# Adafruit_MagTag_2_9in_Rev_D.net
KiCad netlist of a schematic drawn in EAGLE
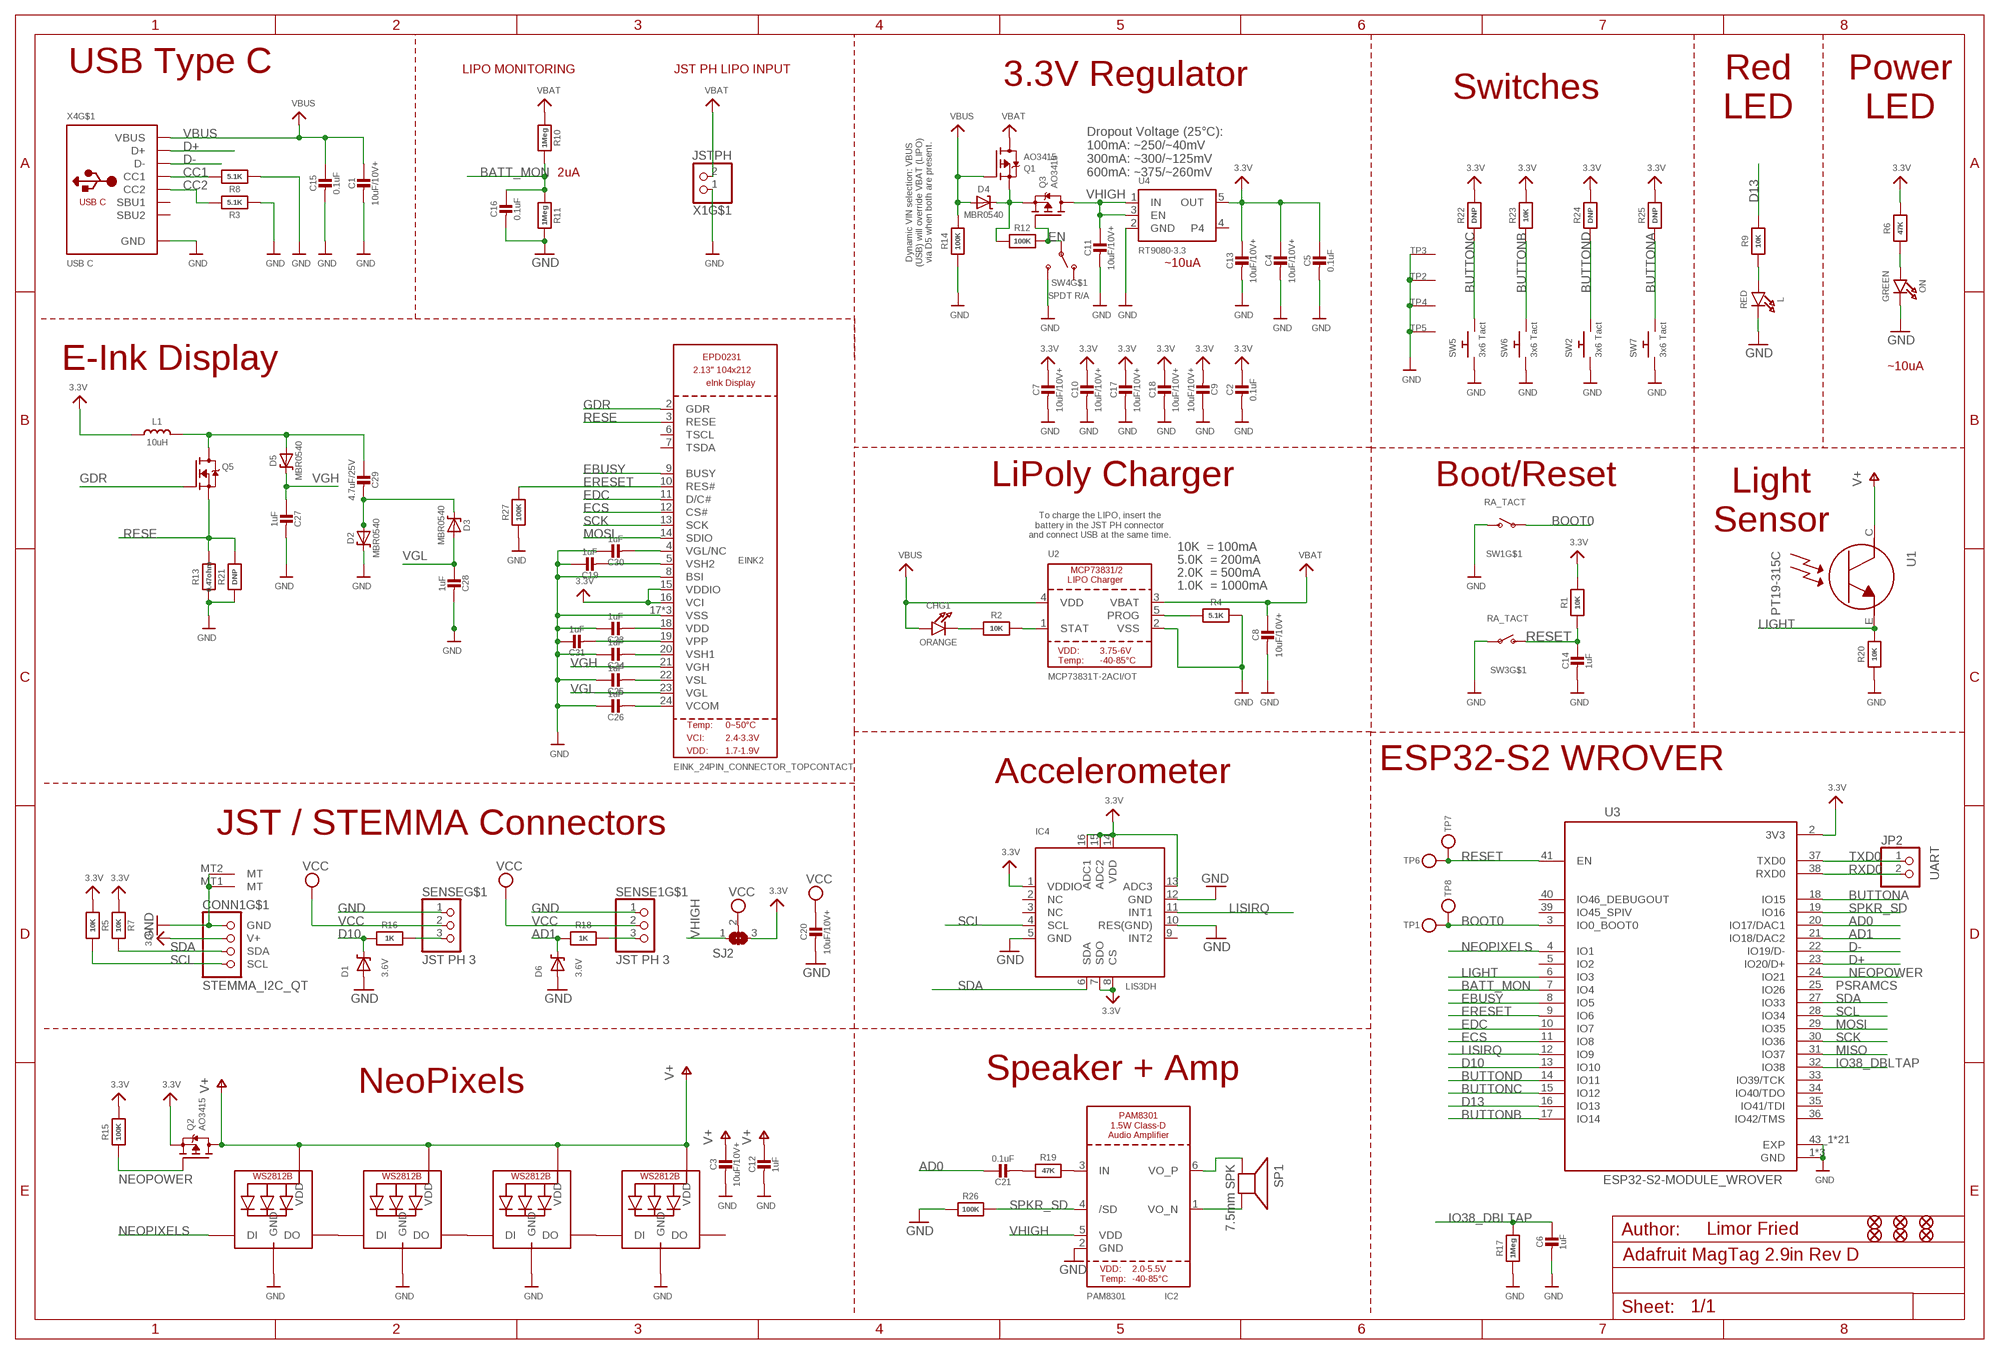
[diagram p0: schematic, sheet 1]

(export (version "E")
  (design (tool "Eeschema 10.0.6"))
  (components
    (comp (ref "C1")
      (value "10uF/10V+")
      (footprint "eagle-import:0805-NO")
      (libsource (lib "eagle-import") (part "CAP_CERAMIC0805-NOOUTLINE"))
    )
    (comp (ref "C2")
      (value "0.1uF")
      (footprint "eagle-import:0603-NO")
      (libsource (lib "eagle-import") (part "CAP_CERAMIC0603_NO"))
    )
    (comp (ref "C3")
      (value "10uF/10V+")
      (footprint "eagle-import:0805-NO")
      (libsource (lib "eagle-import") (part "CAP_CERAMIC0805-NOOUTLINE"))
    )
    (comp (ref "C4")
      (value "10uF/10V+")
      (footprint "eagle-import:0805-NO")
      (libsource (lib "eagle-import") (part "CAP_CERAMIC0805-NOOUTLINE"))
    )
    (comp (ref "C5")
      (value "0.1uF")
      (footprint "eagle-import:0603-NO")
      (libsource (lib "eagle-import") (part "CAP_CERAMIC0603_NO"))
    )
    (comp (ref "C6")
      (value "1uF")
      (footprint "eagle-import:0603-NO")
      (libsource (lib "eagle-import") (part "CAP_CERAMIC0603_NO"))
    )
    (comp (ref "C7")
      (value "10uF/10V+")
      (footprint "eagle-import:0805-NO")
      (libsource (lib "eagle-import") (part "CAP_CERAMIC0805-NOOUTLINE"))
    )
    (comp (ref "C8")
      (value "10uF/10V+")
      (footprint "eagle-import:0805-NO")
      (libsource (lib "eagle-import") (part "CAP_CERAMIC0805-NOOUTLINE"))
    )
    (comp (ref "C9")
      (value "10uF/10V+")
      (footprint "eagle-import:0805-NO")
      (libsource (lib "eagle-import") (part "CAP_CERAMIC0805-NOOUTLINE"))
    )
    (comp (ref "C10")
      (value "10uF/10V+")
      (footprint "eagle-import:0805-NO")
      (libsource (lib "eagle-import") (part "CAP_CERAMIC0805-NOOUTLINE"))
    )
    (comp (ref "C11")
      (value "10uF/10V+")
      (footprint "eagle-import:0805-NO")
      (libsource (lib "eagle-import") (part "CAP_CERAMIC0805-NOOUTLINE"))
    )
    (comp (ref "C12")
      (value "1uF")
      (footprint "eagle-import:0603-NO")
      (libsource (lib "eagle-import") (part "CAP_CERAMIC0603_NO"))
    )
    (comp (ref "C13")
      (value "10uF/10V+")
      (footprint "eagle-import:0805-NO")
      (libsource (lib "eagle-import") (part "CAP_CERAMIC0805-NOOUTLINE"))
    )
    (comp (ref "C14")
      (value "1uF")
      (footprint "eagle-import:0603-NO")
      (libsource (lib "eagle-import") (part "CAP_CERAMIC0603_NO"))
    )
    (comp (ref "C15")
      (value "0.1uF")
      (footprint "eagle-import:0603-NO")
      (libsource (lib "eagle-import") (part "CAP_CERAMIC0603_NO"))
    )
    (comp (ref "C16")
      (value "0.1uF")
      (footprint "eagle-import:0603-NO")
      (libsource (lib "eagle-import") (part "CAP_CERAMIC0603_NO"))
    )
    (comp (ref "C17")
      (value "10uF/10V+")
      (footprint "eagle-import:0805-NO")
      (libsource (lib "eagle-import") (part "CAP_CERAMIC0805-NOOUTLINE"))
    )
    (comp (ref "C18")
      (value "10uF/10V+")
      (footprint "eagle-import:0805-NO")
      (libsource (lib "eagle-import") (part "CAP_CERAMIC0805-NOOUTLINE"))
    )
    (comp (ref "C19")
      (value "1uF")
      (footprint "eagle-import:0805-NO")
      (libsource (lib "eagle-import") (part "CAP_CERAMIC0805-NOOUTLINE"))
    )
    (comp (ref "C20")
      (value "10uF/10V+")
      (footprint "eagle-import:0805-NO")
      (libsource (lib "eagle-import") (part "CAP_CERAMIC0805-NOOUTLINE"))
    )
    (comp (ref "C21")
      (value "0.1uF")
      (footprint "eagle-import:0603-NO")
      (libsource (lib "eagle-import") (part "CAP_CERAMIC0603_NO"))
    )
    (comp (ref "C23")
      (value "1uF")
      (footprint "eagle-import:0805-NO")
      (libsource (lib "eagle-import") (part "CAP_CERAMIC0805-NOOUTLINE"))
    )
    (comp (ref "C24")
      (value "1uF")
      (footprint "eagle-import:0805-NO")
      (libsource (lib "eagle-import") (part "CAP_CERAMIC0805-NOOUTLINE"))
    )
    (comp (ref "C25")
      (value "1uF")
      (footprint "eagle-import:0805-NO")
      (libsource (lib "eagle-import") (part "CAP_CERAMIC0805-NOOUTLINE"))
    )
    (comp (ref "C26")
      (value "1uF")
      (footprint "eagle-import:0805-NO")
      (libsource (lib "eagle-import") (part "CAP_CERAMIC0805-NOOUTLINE"))
    )
    (comp (ref "C27")
      (value "1uF")
      (footprint "eagle-import:0805-NO")
      (libsource (lib "eagle-import") (part "CAP_CERAMIC0805-NOOUTLINE"))
    )
    (comp (ref "C28")
      (value "1uF")
      (footprint "eagle-import:0805-NO")
      (libsource (lib "eagle-import") (part "CAP_CERAMIC0805-NOOUTLINE"))
    )
    (comp (ref "C29")
      (value "4.7uF/25V")
      (footprint "eagle-import:0805-NO")
      (libsource (lib "eagle-import") (part "CAP_CERAMIC0805-NOOUTLINE"))
    )
    (comp (ref "C30")
      (value "1uF")
      (footprint "eagle-import:0805-NO")
      (libsource (lib "eagle-import") (part "CAP_CERAMIC0805-NOOUTLINE"))
    )
    (comp (ref "C31")
      (value "1uF")
      (footprint "eagle-import:0805-NO")
      (libsource (lib "eagle-import") (part "CAP_CERAMIC0805-NOOUTLINE"))
    )
    (comp (ref "CHG1")
      (value "ORANGE")
      (footprint "eagle-import:CHIPLED_0603_NOOUTLINE")
      (libsource (lib "eagle-import") (part "LED0603_NOOUTLINE"))
    )
    (comp (ref "CONN1")
      (value "STEMMA_I2C_QT")
      (footprint "eagle-import:JST_SH4")
      (libsource (lib "eagle-import") (part "STEMMA_I2C_QT"))
    )
    (comp (ref "D1")
      (value "3.6V")
      (footprint "eagle-import:SOD-323")
      (libsource (lib "eagle-import") (part "DIODE-ZENERSOD323"))
    )
    (comp (ref "D2")
      (value "MBR0540")
      (footprint "eagle-import:SOD-123")
      (libsource (lib "eagle-import") (part "DIODE-SCHOTTKYSOD-123"))
    )
    (comp (ref "D3")
      (value "MBR0540")
      (footprint "eagle-import:SOD-123")
      (libsource (lib "eagle-import") (part "DIODE-SCHOTTKYSOD-123"))
    )
    (comp (ref "D4")
      (value "MBR0540")
      (footprint "eagle-import:SOD-123")
      (libsource (lib "eagle-import") (part "DIODE-SCHOTTKYSOD-123"))
    )
    (comp (ref "D5")
      (value "MBR0540")
      (footprint "eagle-import:SOD-123")
      (libsource (lib "eagle-import") (part "DIODE-SCHOTTKYSOD-123"))
    )
    (comp (ref "D6")
      (value "3.6V")
      (footprint "eagle-import:SOD-323")
      (libsource (lib "eagle-import") (part "DIODE-ZENERSOD323"))
    )
    (comp (ref "EINK2")
      (value "EINK_24PIN_CONNECTOR_TOPCONTACT")
      (footprint "eagle-import:EINK_24PIN_TOPCONTACT")
      (libsource (lib "eagle-import") (part "EINK_24PIN_CONNECTOR_TOPCONTACT"))
    )
    (comp (ref "FID1")
      (value "FIDUCIAL_1MM")
      (footprint "eagle-import:FIDUCIAL_1MM")
      (libsource (lib "eagle-import") (part "FIDUCIAL_1MM"))
    )
    (comp (ref "FID2")
      (value "FIDUCIAL_1MM")
      (footprint "eagle-import:FIDUCIAL_1MM")
      (libsource (lib "eagle-import") (part "FIDUCIAL_1MM"))
    )
    (comp (ref "FID3")
      (value "FIDUCIAL_1MM")
      (footprint "eagle-import:FIDUCIAL_1MM")
      (libsource (lib "eagle-import") (part "FIDUCIAL_1MM"))
    )
    (comp (ref "FID4")
      (value "FIDUCIAL_1MM")
      (footprint "eagle-import:FIDUCIAL_1MM")
      (libsource (lib "eagle-import") (part "FIDUCIAL_1MM"))
    )
    (comp (ref "FID5")
      (value "FIDUCIAL_1MM")
      (footprint "eagle-import:FIDUCIAL_1MM")
      (libsource (lib "eagle-import") (part "FIDUCIAL_1MM"))
    )
    (comp (ref "FID6")
      (value "FIDUCIAL_1MM")
      (footprint "eagle-import:FIDUCIAL_1MM")
      (libsource (lib "eagle-import") (part "FIDUCIAL_1MM"))
    )
    (comp (ref "IC2")
      (value "PAM8301")
      (footprint "eagle-import:SOT23-6")
      (libsource (lib "eagle-import") (part "PAM8301"))
    )
    (comp (ref "IC4")
      (value "LIS3DH")
      (footprint "eagle-import:LGA16_3X3MM")
      (libsource (lib "eagle-import") (part "ACCEL_LIS3DHTR"))
    )
    (comp (ref "JP2")
      (value "UART")
      (footprint "eagle-import:1X02_ROUND")
      (libsource (lib "eagle-import") (part "HEADER-1X2ROUND"))
    )
    (comp (ref "L")
      (value "RED")
      (footprint "eagle-import:CHIPLED_0603_NOOUTLINE")
      (libsource (lib "eagle-import") (part "LED0603_NOOUTLINE"))
    )
    (comp (ref "L1")
      (value "10uH")
      (footprint "eagle-import:INDUCTOR_4X4MM_NR401")
      (libsource (lib "eagle-import") (part "INDUCTORNR401"))
    )
    (comp (ref "LED2")
      (value "WS2812B_4020")
      (footprint "eagle-import:WS2812B_4020")
      (libsource (lib "eagle-import") (part "WS2812B_4020"))
    )
    (comp (ref "LED3")
      (value "WS2812B_4020")
      (footprint "eagle-import:WS2812B_4020")
      (libsource (lib "eagle-import") (part "WS2812B_4020"))
    )
    (comp (ref "LED4")
      (value "WS2812B_4020")
      (footprint "eagle-import:WS2812B_4020")
      (libsource (lib "eagle-import") (part "WS2812B_4020"))
    )
    (comp (ref "LED5")
      (value "WS2812B_4020")
      (footprint "eagle-import:WS2812B_4020")
      (libsource (lib "eagle-import") (part "WS2812B_4020"))
    )
    (comp (ref "ON")
      (value "GREEN")
      (footprint "eagle-import:CHIPLED_0603_NOOUTLINE")
      (libsource (lib "eagle-import") (part "LED0603_NOOUTLINE"))
    )
    (comp (ref "Q1")
      (value "AO3415")
      (footprint "eagle-import:SOT23-R")
      (libsource (lib "eagle-import") (part "MOSFET-P"))
    )
    (comp (ref "Q2")
      (value "AO3415")
      (footprint "eagle-import:SOT23-R")
      (libsource (lib "eagle-import") (part "MOSFET-P"))
    )
    (comp (ref "Q3")
      (value "AO3415")
      (footprint "eagle-import:SOT23-R")
      (libsource (lib "eagle-import") (part "MOSFET-P"))
    )
    (comp (ref "Q5")
      (value "IRLML0100")
      (footprint "eagle-import:SOT23-3")
      (libsource (lib "eagle-import") (part "IRLML2060TRPBF"))
    )
    (comp (ref "R1")
      (value "10K")
      (footprint "eagle-import:0603-NO")
      (libsource (lib "eagle-import") (part "RESISTOR_0603_NOOUT"))
    )
    (comp (ref "R2")
      (value "10K")
      (footprint "eagle-import:0603-NO")
      (libsource (lib "eagle-import") (part "RESISTOR_0603_NOOUT"))
    )
    (comp (ref "R3")
      (value "5.1K")
      (footprint "eagle-import:0603-NO")
      (libsource (lib "eagle-import") (part "RESISTOR_0603_NOOUT"))
    )
    (comp (ref "R4")
      (value "5.1K")
      (footprint "eagle-import:0603-NO")
      (libsource (lib "eagle-import") (part "RESISTOR_0603_NOOUT"))
    )
    (comp (ref "R5")
      (value "10K")
      (footprint "eagle-import:0603-NO")
      (libsource (lib "eagle-import") (part "RESISTOR_0603_NOOUT"))
    )
    (comp (ref "R6")
      (value "47K")
      (footprint "eagle-import:0603-NO")
      (libsource (lib "eagle-import") (part "RESISTOR_0603_NOOUT"))
    )
    (comp (ref "R7")
      (value "10K")
      (footprint "eagle-import:0603-NO")
      (libsource (lib "eagle-import") (part "RESISTOR_0603_NOOUT"))
    )
    (comp (ref "R8")
      (value "5.1K")
      (footprint "eagle-import:0603-NO")
      (libsource (lib "eagle-import") (part "RESISTOR_0603_NOOUT"))
    )
    (comp (ref "R9")
      (value "10K")
      (footprint "eagle-import:0603-NO")
      (libsource (lib "eagle-import") (part "RESISTOR_0603_NOOUT"))
    )
    (comp (ref "R10")
      (value "1Meg")
      (footprint "eagle-import:0603-NO")
      (libsource (lib "eagle-import") (part "RESISTOR_0603_NOOUT"))
    )
    (comp (ref "R11")
      (value "1Meg")
      (footprint "eagle-import:0603-NO")
      (libsource (lib "eagle-import") (part "RESISTOR_0603_NOOUT"))
    )
    (comp (ref "R12")
      (value "100K")
      (footprint "eagle-import:0603-NO")
      (libsource (lib "eagle-import") (part "RESISTOR_0603_NOOUT"))
    )
    (comp (ref "R13")
      (value "0.47ohm")
      (footprint "eagle-import:0805_10MGAP")
      (libsource (lib "eagle-import") (part "RESISTOR0805_10MGAP"))
    )
    (comp (ref "R14")
      (value "100K")
      (footprint "eagle-import:0603-NO")
      (libsource (lib "eagle-import") (part "RESISTOR_0603_NOOUT"))
    )
    (comp (ref "R15")
      (value "100K")
      (footprint "eagle-import:0603-NO")
      (libsource (lib "eagle-import") (part "RESISTOR_0603_NOOUT"))
    )
    (comp (ref "R16")
      (value "1K")
      (footprint "eagle-import:0603-NO")
      (libsource (lib "eagle-import") (part "RESISTOR_0603_NOOUT"))
    )
    (comp (ref "R17")
      (value "1Meg")
      (footprint "eagle-import:0603-NO")
      (libsource (lib "eagle-import") (part "RESISTOR_0603_NOOUT"))
    )
    (comp (ref "R18")
      (value "1K")
      (footprint "eagle-import:0603-NO")
      (libsource (lib "eagle-import") (part "RESISTOR_0603_NOOUT"))
    )
    (comp (ref "R19")
      (value "47K")
      (footprint "eagle-import:0603-NO")
      (libsource (lib "eagle-import") (part "RESISTOR_0603_NOOUT"))
    )
    (comp (ref "R20")
      (value "10K")
      (footprint "eagle-import:0603-NO")
      (libsource (lib "eagle-import") (part "RESISTOR_0603_NOOUT"))
    )
    (comp (ref "R21")
      (value "DNP")
      (footprint "eagle-import:0805_10MGAP")
      (libsource (lib "eagle-import") (part "RESISTOR0805_10MGAP"))
    )
    (comp (ref "R22")
      (value "DNP")
      (footprint "eagle-import:0603-NO")
      (libsource (lib "eagle-import") (part "RESISTOR_0603_NOOUT"))
    )
    (comp (ref "R23")
      (value "10K")
      (footprint "eagle-import:0603-NO")
      (libsource (lib "eagle-import") (part "RESISTOR_0603_NOOUT"))
    )
    (comp (ref "R24")
      (value "DNP")
      (footprint "eagle-import:0603-NO")
      (libsource (lib "eagle-import") (part "RESISTOR_0603_NOOUT"))
    )
    (comp (ref "R25")
      (value "DNP")
      (footprint "eagle-import:0603-NO")
      (libsource (lib "eagle-import") (part "RESISTOR_0603_NOOUT"))
    )
    (comp (ref "R26")
      (value "100K")
      (footprint "eagle-import:0603-NO")
      (libsource (lib "eagle-import") (part "RESISTOR_0603_NOOUT"))
    )
    (comp (ref "R27")
      (value "100K")
      (footprint "eagle-import:0603-NO")
      (libsource (lib "eagle-import") (part "RESISTOR_0603_NOOUT"))
    )
    (comp (ref "SENSE")
      (value "JST PH 3")
      (footprint "eagle-import:JSTPH3")
      (libsource (lib "eagle-import") (part "CON_JST_PH_3PIN"))
    )
    (comp (ref "SENSE1")
      (value "JST PH 3")
      (footprint "eagle-import:JSTPH3")
      (libsource (lib "eagle-import") (part "CON_JST_PH_3PIN"))
    )
    (comp (ref "SJ2")
      (value "SOLDERJUMPER_2WAY")
      (footprint "eagle-import:SOLDERJUMPER_2WAY_OPEN_NOPASTE")
      (libsource (lib "eagle-import") (part "SOLDERJUMPER_2WAY"))
    )
    (comp (ref "SP1")
      (value "7.5mm SPK")
      (footprint "eagle-import:BUZZER_SMT_7.5MM")
      (libsource (lib "eagle-import") (part "SPEAKER_7.5MM"))
    )
    (comp (ref "SW1")
      (value "RA_TACT")
      (footprint "eagle-import:SPST_TACTILE_RA")
      (libsource (lib "eagle-import") (part "SWITCH_SPST_MNT_TACT_RA"))
    )
    (comp (ref "SW2")
      (value "3x6 Tact")
      (footprint "eagle-import:TACTILE_3X6MM")
      (libsource (lib "eagle-import") (part "SWITCH_PUSHBUTTON_3.5X6MM"))
    )
    (comp (ref "SW3")
      (value "RA_TACT")
      (footprint "eagle-import:SPST_TACTILE_RA")
      (libsource (lib "eagle-import") (part "SWITCH_SPST_MNT_TACT_RA"))
    )
    (comp (ref "SW4")
      (value "SPDT R/A")
      (footprint "eagle-import:SPDT_SMT_SSSS811101")
      (libsource (lib "eagle-import") (part "SWITCH_SPDT"))
    )
    (comp (ref "SW5")
      (value "3x6 Tact")
      (footprint "eagle-import:TACTILE_3X6MM")
      (libsource (lib "eagle-import") (part "SWITCH_PUSHBUTTON_3.5X6MM"))
    )
    (comp (ref "SW6")
      (value "3x6 Tact")
      (footprint "eagle-import:TACTILE_3X6MM")
      (libsource (lib "eagle-import") (part "SWITCH_PUSHBUTTON_3.5X6MM"))
    )
    (comp (ref "SW7")
      (value "3x6 Tact")
      (footprint "eagle-import:TACTILE_3X6MM")
      (libsource (lib "eagle-import") (part "SWITCH_PUSHBUTTON_3.5X6MM"))
    )
    (comp (ref "TP1")
      (value "TESTPOINTROUND1.5MMNO")
      (footprint "eagle-import:TESTPOINT_ROUND_1.5MM_NO")
      (libsource (lib "eagle-import") (part "TESTPOINTROUND1.5MMNO"))
    )
    (comp (ref "TP2")
      (value "SEWTAP_SMTNUTM3")
      (footprint "eagle-import:SMT_NUT_3MM")
      (libsource (lib "eagle-import") (part "SEWTAP_SMTNUTM3"))
    )
    (comp (ref "TP3")
      (value "SEWTAP_SMTNUTM3")
      (footprint "eagle-import:SMT_NUT_3MM")
      (libsource (lib "eagle-import") (part "SEWTAP_SMTNUTM3"))
    )
    (comp (ref "TP4")
      (value "SEWTAP_SMTNUTM3")
      (footprint "eagle-import:SMT_NUT_3MM")
      (libsource (lib "eagle-import") (part "SEWTAP_SMTNUTM3"))
    )
    (comp (ref "TP5")
      (value "SEWTAP_SMTNUTM3")
      (footprint "eagle-import:SMT_NUT_3MM")
      (libsource (lib "eagle-import") (part "SEWTAP_SMTNUTM3"))
    )
    (comp (ref "TP6")
      (value "TESTPOINTROUND1.5MMNO")
      (footprint "eagle-import:TESTPOINT_ROUND_1.5MM_NO")
      (libsource (lib "eagle-import") (part "TESTPOINTROUND1.5MMNO"))
    )
    (comp (ref "TP7")
      (value "TESTPOINTROUND1.5MMNO")
      (footprint "eagle-import:TESTPOINT_ROUND_1.5MM_NO")
      (libsource (lib "eagle-import") (part "TESTPOINTROUND1.5MMNO"))
    )
    (comp (ref "TP8")
      (value "TESTPOINTROUND1.5MMNO")
      (footprint "eagle-import:TESTPOINT_ROUND_1.5MM_NO")
      (libsource (lib "eagle-import") (part "TESTPOINTROUND1.5MMNO"))
    )
    (comp (ref "U1")
      (value "PT19-315C")
      (footprint "eagle-import:ALS-PT19-315C")
      (libsource (lib "eagle-import") (part "PHOTOTRANSISTOR_PT19-315C"))
    )
    (comp (ref "U2")
      (value "MCP73831T-2ACI/OT")
      (footprint "eagle-import:SOT23-5")
      (libsource (lib "eagle-import") (part "MCP73831/2"))
    )
    (comp (ref "U3")
      (value "ESP32-S2-MODULE_WROVER")
      (footprint "eagle-import:MODULE_ESP32-S2-WROVER")
      (fields (field (name "MF") "Espressif Systems") (field (name "MP") "ESP32-S2-WROVER"))
      (libsource (lib "eagle-import") (part "ESP32-S2-MODULE_WROVER"))
    )
    (comp (ref "U4")
      (value "RT9080-3.3")
      (footprint "eagle-import:SOT23-5")
      (fields (field (name "JLC_ROTATION") "0"))
      (libsource (lib "eagle-import") (part "VREG_SOT23-5"))
    )
    (comp (ref "X1")
      (value "JSTPH")
      (footprint "eagle-import:JSTPH2_BATT")
      (libsource (lib "eagle-import") (part "CON_JST_PH_2PIN_MT_BATT"))
    )
    (comp (ref "X4")
      (value "USB C")
      (footprint "eagle-import:USB_C_CUSB31-CFM2AX-01-X")
      (libsource (lib "eagle-import") (part "USB_C"))
    )
  )
  (nets
    (net (code "1") (name "/AD0") (class "Default")
      (node (ref "C21") (pin "1") (pinfunction "1_1") (pintype "passive"))
      (node (ref "U3") (pin "20") (pinfunction "IO17/DAC1_20") (pintype "bidirectional"))
    )
    (net (code "2") (name "/AD1") (class "Default")
      (node (ref "D6") (pin "C") (pinfunction "C_C") (pintype "passive"))
      (node (ref "R18") (pin "2") (pinfunction "2_2") (pintype "passive"))
      (node (ref "U3") (pin "21") (pinfunction "IO18/DAC2_21") (pintype "bidirectional"))
    )
    (net (code "3") (name "/BATT_MON") (class "Default")
      (node (ref "C16") (pin "1") (pinfunction "1_1") (pintype "passive"))
      (node (ref "R10") (pin "2") (pinfunction "2_2") (pintype "passive"))
      (node (ref "R11") (pin "1") (pinfunction "1_1") (pintype "passive"))
      (node (ref "U3") (pin "7") (pinfunction "IO4_7") (pintype "bidirectional"))
    )
    (net (code "4") (name "/BOOT0") (class "Default")
      (node (ref "SW1") (pin "1") (pinfunction "P_1") (pintype "passive"))
      (node (ref "TP1") (pin "P$1") (pinfunction "P$1_P$1") (pintype "bidirectional"))
      (node (ref "TP8") (pin "P$1") (pinfunction "P$1_P$1") (pintype "bidirectional"))
      (node (ref "U3") (pin "3") (pinfunction "IO0_BOOT0_3") (pintype "bidirectional"))
    )
    (net (code "5") (name "/BUTTONA") (class "Default")
      (node (ref "R25") (pin "1") (pinfunction "1_1") (pintype "passive"))
      (node (ref "SW7") (pin "P$2") (pinfunction "P$2_P$2") (pintype "passive"))
      (node (ref "U3") (pin "18") (pinfunction "IO15_18") (pintype "bidirectional"))
    )
    (net (code "6") (name "/BUTTONB") (class "Default")
      (node (ref "R23") (pin "1") (pinfunction "1_1") (pintype "passive"))
      (node (ref "SW6") (pin "P$2") (pinfunction "P$2_P$2") (pintype "passive"))
      (node (ref "U3") (pin "17") (pinfunction "IO14_17") (pintype "bidirectional"))
    )
    (net (code "7") (name "/BUTTONC") (class "Default")
      (node (ref "R22") (pin "1") (pinfunction "1_1") (pintype "passive"))
      (node (ref "SW5") (pin "P$2") (pinfunction "P$2_P$2") (pintype "passive"))
      (node (ref "U3") (pin "15") (pinfunction "IO12_15") (pintype "bidirectional"))
    )
    (net (code "8") (name "/BUTTOND") (class "Default")
      (node (ref "R24") (pin "1") (pinfunction "1_1") (pintype "passive"))
      (node (ref "SW2") (pin "P$2") (pinfunction "P$2_P$2") (pintype "passive"))
      (node (ref "U3") (pin "14") (pinfunction "IO11_14") (pintype "bidirectional"))
    )
    (net (code "9") (name "/CC1") (class "Default")
      (node (ref "R8") (pin "2") (pinfunction "2_2") (pintype "passive"))
      (node (ref "X4") (pin "A5") (pinfunction "CC1_A5") (pintype "bidirectional"))
    )
    (net (code "10") (name "/CC2") (class "Default")
      (node (ref "R3") (pin "2") (pinfunction "2_2") (pintype "passive"))
      (node (ref "X4") (pin "B5") (pinfunction "CC2_B5") (pintype "bidirectional"))
    )
    (net (code "11") (name "/D+") (class "Default")
      (node (ref "U3") (pin "23") (pinfunction "IO20/D+_23") (pintype "bidirectional"))
      (node (ref "X4") (pin "A6") (pinfunction "D+_A6") (pintype "bidirectional"))
      (node (ref "X4") (pin "B6") (pinfunction "D+_B6") (pintype "bidirectional"))
    )
    (net (code "12") (name "/D-") (class "Default")
      (node (ref "U3") (pin "22") (pinfunction "IO19/D-_22") (pintype "bidirectional"))
      (node (ref "X4") (pin "A7") (pinfunction "D-_A7") (pintype "bidirectional"))
      (node (ref "X4") (pin "B7") (pinfunction "D-_B7") (pintype "bidirectional"))
    )
    (net (code "13") (name "/D10") (class "Default")
      (node (ref "D1") (pin "C") (pinfunction "C_C") (pintype "passive"))
      (node (ref "R16") (pin "2") (pinfunction "2_2") (pintype "passive"))
      (node (ref "U3") (pin "13") (pinfunction "IO10_13") (pintype "bidirectional"))
    )
    (net (code "14") (name "/D13") (class "Default")
      (node (ref "R9") (pin "2") (pinfunction "2_2") (pintype "passive"))
      (node (ref "U3") (pin "16") (pinfunction "IO13_16") (pintype "bidirectional"))
    )
    (net (code "15") (name "/EBUSY") (class "Default")
      (node (ref "EINK2") (pin "9") (pinfunction "BUSY_9") (pintype "output"))
      (node (ref "U3") (pin "8") (pinfunction "IO5_8") (pintype "bidirectional"))
    )
    (net (code "16") (name "/ECS") (class "Default")
      (node (ref "EINK2") (pin "12") (pinfunction "CS#_12") (pintype "input"))
      (node (ref "U3") (pin "11") (pinfunction "IO8_11") (pintype "bidirectional"))
    )
    (net (code "17") (name "/EDC") (class "Default")
      (node (ref "EINK2") (pin "11") (pinfunction "D/C#_11") (pintype "input"))
      (node (ref "U3") (pin "10") (pinfunction "IO7_10") (pintype "bidirectional"))
    )
    (net (code "18") (name "/EN") (class "Default")
      (node (ref "Q3") (pin "1") (pinfunction "G_1") (pintype "passive"))
      (node (ref "R12") (pin "2") (pinfunction "2_2") (pintype "passive"))
      (node (ref "SW4") (pin "B") (pinfunction "P_B") (pintype "passive"))
    )
    (net (code "19") (name "/ERESET") (class "Default")
      (node (ref "EINK2") (pin "10") (pinfunction "RES#_10") (pintype "input"))
      (node (ref "R27") (pin "2") (pinfunction "2_2") (pintype "passive"))
      (node (ref "U3") (pin "9") (pinfunction "IO6_9") (pintype "bidirectional"))
    )
    (net (code "20") (name "/GDR") (class "Default")
      (node (ref "EINK2") (pin "2") (pinfunction "GDR_2") (pintype "output"))
      (node (ref "Q5") (pin "1") (pinfunction "G_1") (pintype "bidirectional"))
    )
    (net (code "21") (name "/IO38_DBLTAP") (class "Default")
      (node (ref "C6") (pin "1") (pinfunction "1_1") (pintype "passive"))
      (node (ref "R17") (pin "2") (pinfunction "2_2") (pintype "passive"))
      (node (ref "U3") (pin "32") (pinfunction "IO38_32") (pintype "bidirectional"))
    )
    (net (code "22") (name "/LIGHT") (class "Default")
      (node (ref "R20") (pin "2") (pinfunction "2_2") (pintype "passive"))
      (node (ref "U1") (pin "E") (pinfunction "E_E") (pintype "bidirectional"))
      (node (ref "U3") (pin "6") (pinfunction "IO3_6") (pintype "bidirectional"))
    )
    (net (code "23") (name "/LISIRQ") (class "Default")
      (node (ref "IC4") (pin "11") (pinfunction "INT1_11") (pintype "output"))
      (node (ref "U3") (pin "12") (pinfunction "IO9_12") (pintype "bidirectional"))
    )
    (net (code "24") (name "/MISO") (class "Default")
      (node (ref "U3") (pin "31") (pinfunction "IO37_31") (pintype "bidirectional"))
    )
    (net (code "25") (name "/MOSI") (class "Default")
      (node (ref "EINK2") (pin "14") (pinfunction "SDIO_14") (pintype "bidirectional"))
      (node (ref "U3") (pin "29") (pinfunction "IO35_29") (pintype "input"))
    )
    (net (code "26") (name "/NEOPIXELS") (class "Default")
      (node (ref "LED2") (pin "1") (pinfunction "DI_1") (pintype "input"))
      (node (ref "U3") (pin "4") (pinfunction "IO1_4") (pintype "bidirectional"))
    )
    (net (code "27") (name "/NEOPOWER") (class "Default")
      (node (ref "Q2") (pin "1") (pinfunction "G_1") (pintype "passive"))
      (node (ref "R15") (pin "1") (pinfunction "1_1") (pintype "passive"))
      (node (ref "U3") (pin "24") (pinfunction "IO21_24") (pintype "bidirectional"))
    )
    (net (code "28") (name "/RESE") (class "Default")
      (node (ref "EINK2") (pin "3") (pinfunction "RESE_3") (pintype "input"))
      (node (ref "Q5") (pin "2") (pinfunction "S_2") (pintype "bidirectional"))
      (node (ref "R13") (pin "1") (pinfunction "1_1") (pintype "passive"))
      (node (ref "R21") (pin "1") (pinfunction "1_1") (pintype "passive"))
    )
    (net (code "29") (name "/RESET") (class "Default")
      (node (ref "C14") (pin "1") (pinfunction "1_1") (pintype "passive"))
      (node (ref "R1") (pin "1") (pinfunction "1_1") (pintype "passive"))
      (node (ref "SW3") (pin "2") (pinfunction "S_2") (pintype "passive"))
      (node (ref "TP6") (pin "P$1") (pinfunction "P$1_P$1") (pintype "bidirectional"))
      (node (ref "TP7") (pin "P$1") (pinfunction "P$1_P$1") (pintype "bidirectional"))
      (node (ref "U3") (pin "41") (pinfunction "EN_41") (pintype "input"))
    )
    (net (code "30") (name "/RXD0") (class "Default")
      (node (ref "JP2") (pin "2") (pinfunction "2_2") (pintype "passive"))
      (node (ref "U3") (pin "38") (pinfunction "RXD0_38") (pintype "bidirectional"))
    )
    (net (code "31") (name "/SCK") (class "Default")
      (node (ref "EINK2") (pin "13") (pinfunction "SCK_13") (pintype "bidirectional"))
      (node (ref "U3") (pin "30") (pinfunction "IO36_30") (pintype "bidirectional"))
    )
    (net (code "32") (name "/SCL") (class "Default")
      (node (ref "CONN1") (pin "4") (pinfunction "SCL_4") (pintype "passive"))
      (node (ref "IC4") (pin "4") (pinfunction "SCL_4") (pintype "bidirectional"))
      (node (ref "R5") (pin "2") (pinfunction "2_2") (pintype "passive"))
      (node (ref "U3") (pin "28") (pinfunction "IO34_28") (pintype "input"))
    )
    (net (code "33") (name "/SDA") (class "Default")
      (node (ref "CONN1") (pin "3") (pinfunction "SDA_3") (pintype "passive"))
      (node (ref "IC4") (pin "6") (pinfunction "SDA_6") (pintype "bidirectional"))
      (node (ref "R7") (pin "2") (pinfunction "2_2") (pintype "passive"))
      (node (ref "U3") (pin "27") (pinfunction "IO33_27") (pintype "bidirectional"))
    )
    (net (code "34") (name "/SPKR_SD") (class "Default")
      (node (ref "IC2") (pin "4") (pinfunction "/SD_4") (pintype "input"))
      (node (ref "R26") (pin "2") (pinfunction "2_2") (pintype "passive"))
      (node (ref "U3") (pin "19") (pinfunction "IO16_19") (pintype "bidirectional"))
    )
    (net (code "35") (name "/TXD0") (class "Default")
      (node (ref "JP2") (pin "1") (pinfunction "1_1") (pintype "passive"))
      (node (ref "U3") (pin "37") (pinfunction "TXD0_37") (pintype "bidirectional"))
    )
    (net (code "36") (name "/VGH") (class "Default")
      (node (ref "C27") (pin "1") (pinfunction "1_1") (pintype "passive"))
      (node (ref "D5") (pin "C") (pinfunction "C_C") (pintype "passive"))
      (node (ref "EINK2") (pin "21") (pinfunction "VGH_21") (pintype "passive"))
    )
    (net (code "37") (name "/VGL") (class "Default")
      (node (ref "C28") (pin "1") (pinfunction "1_1") (pintype "passive"))
      (node (ref "D3") (pin "A") (pinfunction "A_A") (pintype "passive"))
      (node (ref "EINK2") (pin "23") (pinfunction "VGL_23") (pintype "passive"))
    )
    (net (code "38") (name "/VHIGH") (class "Default")
      (node (ref "C11") (pin "1") (pinfunction "1_1") (pintype "passive"))
      (node (ref "IC2") (pin "5") (pinfunction "VDD_5") (pintype "power_in"))
      (node (ref "Q3") (pin "3") (pinfunction "D_3") (pintype "passive"))
      (node (ref "SJ2") (pin "1") (pinfunction "1_1") (pintype "passive"))
      (node (ref "U4") (pin "1") (pinfunction "IN_1") (pintype "power_in"))
      (node (ref "U4") (pin "3") (pinfunction "EN_3") (pintype "input"))
    )
    (net (code "39") (name "3.3V") (class "Default")
      (node (ref "C10") (pin "1") (pinfunction "1_1") (pintype "passive"))
      (node (ref "C13") (pin "1") (pinfunction "1_1") (pintype "passive"))
      (node (ref "C17") (pin "1") (pinfunction "1_1") (pintype "passive"))
      (node (ref "C18") (pin "1") (pinfunction "1_1") (pintype "passive"))
      (node (ref "C2") (pin "1") (pinfunction "1_1") (pintype "passive"))
      (node (ref "C4") (pin "1") (pinfunction "1_1") (pintype "passive"))
      (node (ref "C5") (pin "1") (pinfunction "1_1") (pintype "passive"))
      (node (ref "C7") (pin "1") (pinfunction "1_1") (pintype "passive"))
      (node (ref "C9") (pin "2") (pinfunction "2_2") (pintype "passive"))
      (node (ref "CONN1") (pin "2") (pinfunction "V+_2") (pintype "passive"))
      (node (ref "EINK2") (pin "15") (pinfunction "VDDIO_15") (pintype "power_in"))
      (node (ref "EINK2") (pin "16") (pinfunction "VCI_16") (pintype "power_in"))
      (node (ref "IC4") (pin "1") (pinfunction "VDDIO_1") (pintype "power_in"))
      (node (ref "IC4") (pin "13") (pinfunction "ADC3_13") (pintype "input"))
      (node (ref "IC4") (pin "14") (pinfunction "VDD_14") (pintype "power_in"))
      (node (ref "IC4") (pin "15") (pinfunction "ADC2_15") (pintype "input"))
      (node (ref "IC4") (pin "16") (pinfunction "ADC1_16") (pintype "input"))
      (node (ref "IC4") (pin "7") (pinfunction "SDO_7") (pintype "bidirectional"))
      (node (ref "IC4") (pin "8") (pinfunction "CS_8") (pintype "input"))
      (node (ref "L1") (pin "P$2") (pinfunction "2_P$2") (pintype "passive"))
      (node (ref "Q2") (pin "2") (pinfunction "S_2") (pintype "passive"))
      (node (ref "R1") (pin "2") (pinfunction "2_2") (pintype "passive"))
      (node (ref "R15") (pin "2") (pinfunction "2_2") (pintype "passive"))
      (node (ref "R22") (pin "2") (pinfunction "2_2") (pintype "passive"))
      (node (ref "R23") (pin "2") (pinfunction "2_2") (pintype "passive"))
      (node (ref "R24") (pin "2") (pinfunction "2_2") (pintype "passive"))
      (node (ref "R25") (pin "2") (pinfunction "2_2") (pintype "passive"))
      (node (ref "R5") (pin "1") (pinfunction "1_1") (pintype "passive"))
      (node (ref "R6") (pin "2") (pinfunction "2_2") (pintype "passive"))
      (node (ref "R7") (pin "1") (pinfunction "1_1") (pintype "passive"))
      (node (ref "SJ2") (pin "3") (pinfunction "3_3") (pintype "passive"))
      (node (ref "U3") (pin "2") (pinfunction "3V3_2") (pintype "power_in"))
      (node (ref "U4") (pin "5") (pinfunction "OUT_5") (pintype "power_in"))
    )
    (net (code "40") (name "GND") (class "Default")
      (node (ref "C1") (pin "2") (pinfunction "2_2") (pintype "passive"))
      (node (ref "C10") (pin "2") (pinfunction "2_2") (pintype "passive"))
      (node (ref "C11") (pin "2") (pinfunction "2_2") (pintype "passive"))
      (node (ref "C12") (pin "2") (pinfunction "2_2") (pintype "passive"))
      (node (ref "C13") (pin "2") (pinfunction "2_2") (pintype "passive"))
      (node (ref "C14") (pin "2") (pinfunction "2_2") (pintype "passive"))
      (node (ref "C15") (pin "2") (pinfunction "2_2") (pintype "passive"))
      (node (ref "C16") (pin "2") (pinfunction "2_2") (pintype "passive"))
      (node (ref "C17") (pin "2") (pinfunction "2_2") (pintype "passive"))
      (node (ref "C18") (pin "2") (pinfunction "2_2") (pintype "passive"))
      (node (ref "C19") (pin "1") (pinfunction "1_1") (pintype "passive"))
      (node (ref "C2") (pin "2") (pinfunction "2_2") (pintype "passive"))
      (node (ref "C20") (pin "2") (pinfunction "2_2") (pintype "passive"))
      (node (ref "C23") (pin "1") (pinfunction "1_1") (pintype "passive"))
      (node (ref "C24") (pin "1") (pinfunction "1_1") (pintype "passive"))
      (node (ref "C25") (pin "1") (pinfunction "1_1") (pintype "passive"))
      (node (ref "C26") (pin "1") (pinfunction "1_1") (pintype "passive"))
      (node (ref "C27") (pin "2") (pinfunction "2_2") (pintype "passive"))
      (node (ref "C28") (pin "2") (pinfunction "2_2") (pintype "passive"))
      (node (ref "C3") (pin "2") (pinfunction "2_2") (pintype "passive"))
      (node (ref "C30") (pin "1") (pinfunction "1_1") (pintype "passive"))
      (node (ref "C31") (pin "1") (pinfunction "1_1") (pintype "passive"))
      (node (ref "C4") (pin "2") (pinfunction "2_2") (pintype "passive"))
      (node (ref "C5") (pin "2") (pinfunction "2_2") (pintype "passive"))
      (node (ref "C6") (pin "2") (pinfunction "2_2") (pintype "passive"))
      (node (ref "C7") (pin "2") (pinfunction "2_2") (pintype "passive"))
      (node (ref "C8") (pin "2") (pinfunction "2_2") (pintype "passive"))
      (node (ref "C9") (pin "1") (pinfunction "1_1") (pintype "passive"))
      (node (ref "CONN1") (pin "1") (pinfunction "GND_1") (pintype "passive"))
      (node (ref "CONN1") (pin "MT1") (pinfunction "MT_MT1") (pintype "bidirectional"))
      (node (ref "CONN1") (pin "MT2") (pinfunction "MT_MT2") (pintype "bidirectional"))
      (node (ref "D1") (pin "A") (pinfunction "A_A") (pintype "passive"))
      (node (ref "D2") (pin "C") (pinfunction "C_C") (pintype "passive"))
      (node (ref "D6") (pin "A") (pinfunction "A_A") (pintype "passive"))
      (node (ref "EINK2") (pin "17") (pinfunction "VSS_17") (pintype "power_in"))
      (node (ref "EINK2") (pin "8") (pinfunction "BSI_8") (pintype "input"))
      (node (ref "EINK2") (pin "SPRT1") (pinfunction "VSS_SPRT1") (pintype "power_in"))
      (node (ref "EINK2") (pin "SPRT2") (pinfunction "VSS_SPRT2") (pintype "power_in"))
      (node (ref "IC2") (pin "2") (pinfunction "GND_2") (pintype "power_in"))
      (node (ref "IC4") (pin "10") (pinfunction "RES(GND)_10") (pintype "bidirectional"))
      (node (ref "IC4") (pin "12") (pinfunction "GND_12") (pintype "power_in"))
      (node (ref "IC4") (pin "5") (pinfunction "GND_5") (pintype "power_in"))
      (node (ref "L") (pin "C") (pinfunction "C_C") (pintype "passive"))
      (node (ref "LED2") (pin "4") (pinfunction "GND_4") (pintype "power_in"))
      (node (ref "LED3") (pin "4") (pinfunction "GND_4") (pintype "power_in"))
      (node (ref "LED4") (pin "4") (pinfunction "GND_4") (pintype "power_in"))
      (node (ref "LED5") (pin "4") (pinfunction "GND_4") (pintype "power_in"))
      (node (ref "ON") (pin "C") (pinfunction "C_C") (pintype "passive"))
      (node (ref "R11") (pin "2") (pinfunction "2_2") (pintype "passive"))
      (node (ref "R13") (pin "2") (pinfunction "2_2") (pintype "passive"))
      (node (ref "R14") (pin "1") (pinfunction "1_1") (pintype "passive"))
      (node (ref "R17") (pin "1") (pinfunction "1_1") (pintype "passive"))
      (node (ref "R20") (pin "1") (pinfunction "1_1") (pintype "passive"))
      (node (ref "R21") (pin "2") (pinfunction "2_2") (pintype "passive"))
      (node (ref "R26") (pin "1") (pinfunction "1_1") (pintype "passive"))
      (node (ref "R27") (pin "1") (pinfunction "1_1") (pintype "passive"))
      (node (ref "R3") (pin "1") (pinfunction "1_1") (pintype "passive"))
      (node (ref "R4") (pin "2") (pinfunction "2_2") (pintype "passive"))
      (node (ref "R8") (pin "1") (pinfunction "1_1") (pintype "passive"))
      (node (ref "SENSE") (pin "1") (pinfunction "1_1") (pintype "passive"))
      (node (ref "SENSE1") (pin "1") (pinfunction "1_1") (pintype "passive"))
      (node (ref "SW1") (pin "2") (pinfunction "S_2") (pintype "passive"))
      (node (ref "SW2") (pin "P$1") (pinfunction "P$1_P$1") (pintype "passive"))
      (node (ref "SW3") (pin "1") (pinfunction "P_1") (pintype "passive"))
      (node (ref "SW4") (pin "C") (pinfunction "S_C") (pintype "passive"))
      (node (ref "SW5") (pin "P$1") (pinfunction "P$1_P$1") (pintype "passive"))
      (node (ref "SW6") (pin "P$1") (pinfunction "P$1_P$1") (pintype "passive"))
      (node (ref "SW7") (pin "P$1") (pinfunction "P$1_P$1") (pintype "passive"))
      (node (ref "TP2") (pin "P$1") (pinfunction "SEW_P$1") (pintype "bidirectional"))
      (node (ref "TP3") (pin "P$1") (pinfunction "SEW_P$1") (pintype "bidirectional"))
      (node (ref "TP4") (pin "P$1") (pinfunction "SEW_P$1") (pintype "bidirectional"))
      (node (ref "TP5") (pin "P$1") (pinfunction "SEW_P$1") (pintype "bidirectional"))
      (node (ref "U2") (pin "2") (pinfunction "VSS_2") (pintype "power_in"))
      (node (ref "U3") (pin "1") (pinfunction "GND_1") (pintype "power_in"))
      (node (ref "U3") (pin "26") (pinfunction "GND_26") (pintype "power_in"))
      (node (ref "U3") (pin "42") (pinfunction "GND_42") (pintype "power_in"))
      (node (ref "U3") (pin "43_1") (pinfunction "EXP_43_1") (pintype "power_in"))
      (node (ref "U3") (pin "43_10") (pinfunction "EXP_43_10") (pintype "power_in"))
      (node (ref "U3") (pin "43_11") (pinfunction "EXP_43_11") (pintype "power_in"))
      (node (ref "U3") (pin "43_12") (pinfunction "EXP_43_12") (pintype "power_in"))
      (node (ref "U3") (pin "43_13") (pinfunction "EXP_43_13") (pintype "power_in"))
      (node (ref "U3") (pin "43_14") (pinfunction "EXP_43_14") (pintype "power_in"))
      (node (ref "U3") (pin "43_15") (pinfunction "EXP_43_15") (pintype "power_in"))
      (node (ref "U3") (pin "43_16") (pinfunction "EXP_43_16") (pintype "power_in"))
      (node (ref "U3") (pin "43_17") (pinfunction "EXP_43_17") (pintype "power_in"))
      (node (ref "U3") (pin "43_18") (pinfunction "EXP_43_18") (pintype "power_in"))
      (node (ref "U3") (pin "43_19") (pinfunction "EXP_43_19") (pintype "power_in"))
      (node (ref "U3") (pin "43_2") (pinfunction "EXP_43_2") (pintype "power_in"))
      (node (ref "U3") (pin "43_20") (pinfunction "EXP_43_20") (pintype "power_in"))
      (node (ref "U3") (pin "43_21") (pinfunction "EXP_43_21") (pintype "power_in"))
      (node (ref "U3") (pin "43_3") (pinfunction "EXP_43_3") (pintype "power_in"))
      (node (ref "U3") (pin "43_4") (pinfunction "EXP_43_4") (pintype "power_in"))
      (node (ref "U3") (pin "43_5") (pinfunction "EXP_43_5") (pintype "power_in"))
      (node (ref "U3") (pin "43_6") (pinfunction "EXP_43_6") (pintype "power_in"))
      (node (ref "U3") (pin "43_7") (pinfunction "EXP_43_7") (pintype "power_in"))
      (node (ref "U3") (pin "43_8") (pinfunction "EXP_43_8") (pintype "power_in"))
      (node (ref "U3") (pin "43_9") (pinfunction "EXP_43_9") (pintype "power_in"))
      (node (ref "U4") (pin "2") (pinfunction "GND_2") (pintype "power_in"))
      (node (ref "X1") (pin "1") (pinfunction "1_1") (pintype "passive"))
      (node (ref "X4") (pin "A1B12") (pinfunction "GND_A1B12") (pintype "power_in"))
      (node (ref "X4") (pin "B1A12") (pinfunction "GND_B1A12") (pintype "power_in"))
    )
    (net (code "41") (name "Net-(C21-Pad2)") (class "Default")
      (node (ref "C21") (pin "2") (pinfunction "2_2") (pintype "passive"))
      (node (ref "R19") (pin "1") (pinfunction "1_1") (pintype "passive"))
    )
    (net (code "42") (name "Net-(C29-Pad2)") (class "Default")
      (node (ref "C29") (pin "2") (pinfunction "2_2") (pintype "passive"))
      (node (ref "D2") (pin "A") (pinfunction "A_A") (pintype "passive"))
      (node (ref "D3") (pin "C") (pinfunction "C_C") (pintype "passive"))
    )
    (net (code "43") (name "Net-(CHG1-PadC)") (class "Default")
      (node (ref "CHG1") (pin "C") (pinfunction "C_C") (pintype "passive"))
      (node (ref "R2") (pin "1") (pinfunction "1_1") (pintype "passive"))
    )
    (net (code "44") (name "Net-(EINK2-VCOM)") (class "Default")
      (node (ref "C26") (pin "2") (pinfunction "2_2") (pintype "passive"))
      (node (ref "EINK2") (pin "24") (pinfunction "VCOM_24") (pintype "passive"))
    )
    (net (code "45") (name "Net-(EINK2-VDD)") (class "Default")
      (node (ref "C23") (pin "2") (pinfunction "2_2") (pintype "passive"))
      (node (ref "EINK2") (pin "18") (pinfunction "VDD_18") (pintype "passive"))
    )
    (net (code "46") (name "Net-(EINK2-VGL{slash}NC)") (class "Default")
      (node (ref "C30") (pin "2") (pinfunction "2_2") (pintype "passive"))
      (node (ref "EINK2") (pin "4") (pinfunction "VGL/NC_4") (pintype "bidirectional"))
    )
    (net (code "47") (name "Net-(EINK2-VPP)") (class "Default")
      (node (ref "C31") (pin "2") (pinfunction "2_2") (pintype "passive"))
      (node (ref "EINK2") (pin "19") (pinfunction "VPP_19") (pintype "passive"))
    )
    (net (code "48") (name "Net-(EINK2-VSH1)") (class "Default")
      (node (ref "C24") (pin "2") (pinfunction "2_2") (pintype "passive"))
      (node (ref "EINK2") (pin "20") (pinfunction "VSH1_20") (pintype "passive"))
    )
    (net (code "49") (name "Net-(EINK2-VSH2)") (class "Default")
      (node (ref "C19") (pin "2") (pinfunction "2_2") (pintype "passive"))
      (node (ref "EINK2") (pin "5") (pinfunction "VSH2_5") (pintype "passive"))
    )
    (net (code "50") (name "Net-(EINK2-VSL)") (class "Default")
      (node (ref "C25") (pin "2") (pinfunction "2_2") (pintype "passive"))
      (node (ref "EINK2") (pin "22") (pinfunction "VSL_22") (pintype "passive"))
    )
    (net (code "51") (name "Net-(IC2-IN)") (class "Default")
      (node (ref "IC2") (pin "3") (pinfunction "IN_3") (pintype "input"))
      (node (ref "R19") (pin "2") (pinfunction "2_2") (pintype "passive"))
    )
    (net (code "52") (name "Net-(IC2-VO_N)") (class "Default")
      (node (ref "IC2") (pin "1") (pinfunction "VO_N_1") (pintype "output"))
      (node (ref "SP1") (pin "-") (pinfunction "-_-") (pintype "passive"))
    )
    (net (code "53") (name "Net-(IC2-VO_P)") (class "Default")
      (node (ref "IC2") (pin "6") (pinfunction "VO_P_6") (pintype "output"))
      (node (ref "SP1") (pin "+") (pinfunction "+_+") (pintype "passive"))
    )
    (net (code "54") (name "Net-(L-PadA)") (class "Default")
      (node (ref "L") (pin "A") (pinfunction "A_A") (pintype "passive"))
      (node (ref "R9") (pin "1") (pinfunction "1_1") (pintype "passive"))
    )
    (net (code "55") (name "Net-(L1-1)") (class "Default")
      (node (ref "C29") (pin "1") (pinfunction "1_1") (pintype "passive"))
      (node (ref "D5") (pin "A") (pinfunction "A_A") (pintype "passive"))
      (node (ref "L1") (pin "P$1") (pinfunction "1_P$1") (pintype "passive"))
      (node (ref "Q5") (pin "3") (pinfunction "D_3") (pintype "bidirectional"))
    )
    (net (code "56") (name "Net-(LED2-DO)") (class "Default")
      (node (ref "LED2") (pin "3") (pinfunction "DO_3") (pintype "output"))
      (node (ref "LED3") (pin "1") (pinfunction "DI_1") (pintype "input"))
    )
    (net (code "57") (name "Net-(LED3-DO)") (class "Default")
      (node (ref "LED3") (pin "3") (pinfunction "DO_3") (pintype "output"))
      (node (ref "LED4") (pin "1") (pinfunction "DI_1") (pintype "input"))
    )
    (net (code "58") (name "Net-(LED4-DO)") (class "Default")
      (node (ref "LED4") (pin "3") (pinfunction "DO_3") (pintype "output"))
      (node (ref "LED5") (pin "1") (pinfunction "DI_1") (pintype "input"))
    )
    (net (code "59") (name "Net-(ON-PadA)") (class "Default")
      (node (ref "ON") (pin "A") (pinfunction "A_A") (pintype "passive"))
      (node (ref "R6") (pin "1") (pinfunction "1_1") (pintype "passive"))
    )
    (net (code "60") (name "Net-(Q1-S)") (class "Default")
      (node (ref "D4") (pin "C") (pinfunction "C_C") (pintype "passive"))
      (node (ref "Q1") (pin "2") (pinfunction "S_2") (pintype "passive"))
      (node (ref "Q3") (pin "2") (pinfunction "S_2") (pintype "passive"))
      (node (ref "R12") (pin "1") (pinfunction "1_1") (pintype "passive"))
    )
    (net (code "61") (name "Net-(R16-Pad1)") (class "Default")
      (node (ref "R16") (pin "1") (pinfunction "1_1") (pintype "passive"))
      (node (ref "SENSE") (pin "3") (pinfunction "3_3") (pintype "passive"))
    )
    (net (code "62") (name "Net-(R18-Pad1)") (class "Default")
      (node (ref "R18") (pin "1") (pinfunction "1_1") (pintype "passive"))
      (node (ref "SENSE1") (pin "3") (pinfunction "3_3") (pintype "passive"))
    )
    (net (code "63") (name "Net-(U2-PROG)") (class "Default")
      (node (ref "R4") (pin "1") (pinfunction "1_1") (pintype "passive"))
      (node (ref "U2") (pin "5") (pinfunction "PROG_5") (pintype "input"))
    )
    (net (code "64") (name "Net-(U2-STAT)") (class "Default")
      (node (ref "R2") (pin "2") (pinfunction "2_2") (pintype "passive"))
      (node (ref "U2") (pin "1") (pinfunction "STAT_1") (pintype "output"))
    )
    (net (code "65") (name "V+") (class "Default")
      (node (ref "C12") (pin "1") (pinfunction "1_1") (pintype "passive"))
      (node (ref "C3") (pin "1") (pinfunction "1_1") (pintype "passive"))
      (node (ref "LED2") (pin "2") (pinfunction "VDD_2") (pintype "power_in"))
      (node (ref "LED3") (pin "2") (pinfunction "VDD_2") (pintype "power_in"))
      (node (ref "LED4") (pin "2") (pinfunction "VDD_2") (pintype "power_in"))
      (node (ref "LED5") (pin "2") (pinfunction "VDD_2") (pintype "power_in"))
      (node (ref "Q2") (pin "3") (pinfunction "D_3") (pintype "passive"))
      (node (ref "U1") (pin "C") (pinfunction "C_C") (pintype "bidirectional"))
    )
    (net (code "66") (name "VBAT") (class "Default")
      (node (ref "C8") (pin "1") (pinfunction "1_1") (pintype "passive"))
      (node (ref "Q1") (pin "3") (pinfunction "D_3") (pintype "passive"))
      (node (ref "R10") (pin "1") (pinfunction "1_1") (pintype "passive"))
      (node (ref "U2") (pin "3") (pinfunction "VBAT_3") (pintype "power_in"))
      (node (ref "X1") (pin "2") (pinfunction "2_2") (pintype "passive"))
    )
    (net (code "67") (name "VBUS") (class "Default")
      (node (ref "C1") (pin "1") (pinfunction "1_1") (pintype "passive"))
      (node (ref "C15") (pin "1") (pinfunction "1_1") (pintype "passive"))
      (node (ref "CHG1") (pin "A") (pinfunction "A_A") (pintype "passive"))
      (node (ref "D4") (pin "A") (pinfunction "A_A") (pintype "passive"))
      (node (ref "Q1") (pin "1") (pinfunction "G_1") (pintype "passive"))
      (node (ref "R14") (pin "2") (pinfunction "2_2") (pintype "passive"))
      (node (ref "U2") (pin "4") (pinfunction "VDD_4") (pintype "power_in"))
      (node (ref "X4") (pin "A4B9") (pinfunction "VBUS_A4B9") (pintype "power_in"))
      (node (ref "X4") (pin "B4A9") (pinfunction "VBUS_B4A9") (pintype "power_in"))
    )
    (net (code "68") (name "VCC") (class "Default")
      (node (ref "C20") (pin "1") (pinfunction "1_1") (pintype "passive"))
      (node (ref "SENSE") (pin "2") (pinfunction "2_2") (pintype "passive"))
      (node (ref "SENSE1") (pin "2") (pinfunction "2_2") (pintype "passive"))
      (node (ref "SJ2") (pin "2") (pinfunction "2_2") (pintype "passive"))
    )
    (net (code "69") (name "unconnected-(EINK2-TSCL-Pad6)") (class "Default")
      (node (ref "EINK2") (pin "6") (pinfunction "TSCL_6") (pintype "output"))
    )
    (net (code "70") (name "unconnected-(EINK2-TSDA-Pad7)") (class "Default")
      (node (ref "EINK2") (pin "7") (pinfunction "TSDA_7") (pintype "bidirectional"))
    )
    (net (code "71") (name "unconnected-(IC4-INT2-Pad9)") (class "Default")
      (node (ref "IC4") (pin "9") (pinfunction "INT2_9") (pintype "output"))
    )
    (net (code "72") (name "unconnected-(IC4-NC-Pad2)") (class "Default")
      (node (ref "IC4") (pin "2") (pinfunction "NC_2") (pintype "no_connect"))
    )
    (net (code "73") (name "unconnected-(IC4-NC-Pad3)") (class "Default")
      (node (ref "IC4") (pin "3") (pinfunction "NC_3") (pintype "no_connect"))
    )
    (net (code "74") (name "unconnected-(LED5-DO-Pad3)") (class "Default")
      (node (ref "LED5") (pin "3") (pinfunction "DO_3") (pintype "output"))
    )
    (net (code "75") (name "unconnected-(SW4A-O-PadA)") (class "Default")
      (node (ref "SW4") (pin "A") (pinfunction "O_A") (pintype "passive"))
    )
    (net (code "76") (name "unconnected-(U3-IO2-Pad5)") (class "Default")
      (node (ref "U3") (pin "5") (pinfunction "IO2_5") (pintype "bidirectional"))
    )
    (net (code "77") (name "unconnected-(U3-IO26-Pad25)") (class "Default")
      (node (ref "U3") (pin "25") (pinfunction "IO26_25") (pintype "bidirectional"))
    )
    (net (code "78") (name "unconnected-(U3-IO39{slash}TCK-Pad33)") (class "Default")
      (node (ref "U3") (pin "33") (pinfunction "IO39/TCK_33") (pintype "bidirectional"))
    )
    (net (code "79") (name "unconnected-(U3-IO40{slash}TDO-Pad34)") (class "Default")
      (node (ref "U3") (pin "34") (pinfunction "IO40/TDO_34") (pintype "bidirectional"))
    )
    (net (code "80") (name "unconnected-(U3-IO41{slash}TDI-Pad35)") (class "Default")
      (node (ref "U3") (pin "35") (pinfunction "IO41/TDI_35") (pintype "bidirectional"))
    )
    (net (code "81") (name "unconnected-(U3-IO42{slash}TMS-Pad36)") (class "Default")
      (node (ref "U3") (pin "36") (pinfunction "IO42/TMS_36") (pintype "bidirectional"))
    )
    (net (code "82") (name "unconnected-(U3-IO45_SPIV-Pad39)") (class "Default")
      (node (ref "U3") (pin "39") (pinfunction "IO45_SPIV_39") (pintype "bidirectional"))
    )
    (net (code "83") (name "unconnected-(U3-IO46_DEBUGOUT-Pad40)") (class "Default")
      (node (ref "U3") (pin "40") (pinfunction "IO46_DEBUGOUT_40") (pintype "input"))
    )
    (net (code "84") (name "unconnected-(U4-P4-Pad4)") (class "Default")
      (node (ref "U4") (pin "4") (pinfunction "P4_4") (pintype "bidirectional"))
    )
    (net (code "85") (name "unconnected-(X4A-SBU1-PadA8)") (class "Default")
      (node (ref "X4") (pin "A8") (pinfunction "SBU1_A8") (pintype "bidirectional"))
    )
    (net (code "86") (name "unconnected-(X4A-SBU2-PadB8)") (class "Default")
      (node (ref "X4") (pin "B8") (pinfunction "SBU2_B8") (pintype "bidirectional"))
    )
  )
)
